# lllc.net
KiCad netlist of a schematic drawn in EAGLE
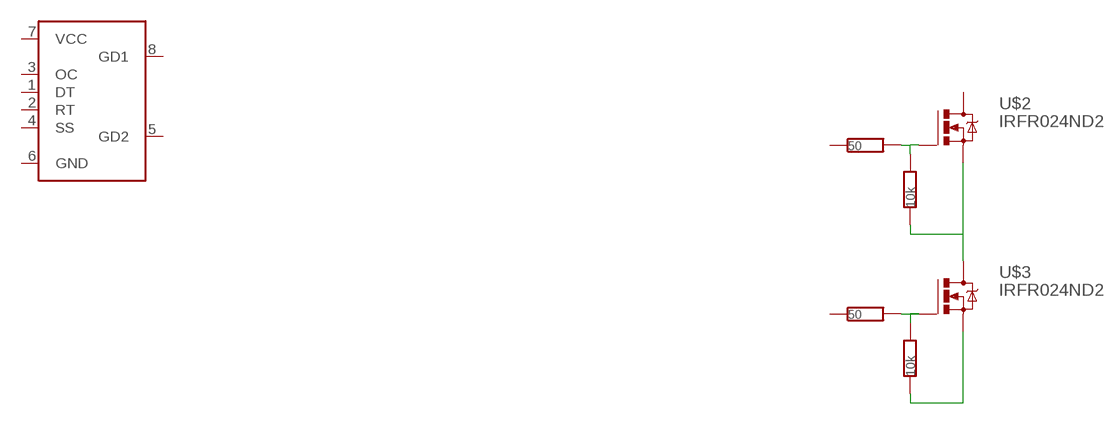
[diagram p0: schematic, sheet 1]

(export (version "E")
  (design (tool "Eeschema 10.0.6"))
  (components
    (comp (ref "R1")
      (value "50")
      (footprint "eagle-import:R0805")
      (libsource (lib "eagle-import") (part "R0805"))
    )
    (comp (ref "R2")
      (value "50")
      (footprint "eagle-import:R0805")
      (libsource (lib "eagle-import") (part "R0805"))
    )
    (comp (ref "R3")
      (value "10k")
      (footprint "eagle-import:R0805")
      (libsource (lib "eagle-import") (part "R0805"))
    )
    (comp (ref "R4")
      (value "10k")
      (footprint "eagle-import:R0805")
      (libsource (lib "eagle-import") (part "R0805"))
    )
    (comp (ref "U$1")
      (value "TPS92020")
      (footprint "eagle-import:SO08")
      (libsource (lib "eagle-import") (part "TPS92020"))
    )
    (comp (ref "U$2")
      (value "IRFR024ND2")
      (footprint "eagle-import:D2PACK")
      (libsource (lib "eagle-import") (part "IRFR024ND2"))
    )
    (comp (ref "U$3")
      (value "IRFR024ND2")
      (footprint "eagle-import:D2PACK")
      (libsource (lib "eagle-import") (part "IRFR024ND2"))
    )
  )
  (nets
    (net (code "1") (name "Net-(U$2-G)") (class "Default")
      (node (ref "R1") (pin "2") (pinfunction "2_2") (pintype "passive"))
      (node (ref "R3") (pin "2") (pinfunction "2_2") (pintype "passive"))
      (node (ref "U$2") (pin "1") (pinfunction "G_1") (pintype "passive"))
    )
    (net (code "2") (name "Net-(U$2-S)") (class "Default")
      (node (ref "R3") (pin "1") (pinfunction "1_1") (pintype "passive"))
      (node (ref "U$2") (pin "3") (pinfunction "S_3") (pintype "passive"))
      (node (ref "U$3") (pin "2") (pinfunction "D_2") (pintype "passive"))
    )
    (net (code "3") (name "Net-(U$3-G)") (class "Default")
      (node (ref "R2") (pin "2") (pinfunction "2_2") (pintype "passive"))
      (node (ref "R4") (pin "2") (pinfunction "2_2") (pintype "passive"))
      (node (ref "U$3") (pin "1") (pinfunction "G_1") (pintype "passive"))
    )
    (net (code "4") (name "Net-(U$3-S)") (class "Default")
      (node (ref "R4") (pin "1") (pinfunction "1_1") (pintype "passive"))
      (node (ref "U$3") (pin "3") (pinfunction "S_3") (pintype "passive"))
    )
    (net (code "5") (name "unconnected-(R1-Pad1)") (class "Default")
      (node (ref "R1") (pin "1") (pinfunction "1_1") (pintype "passive"))
    )
    (net (code "6") (name "unconnected-(R2-Pad1)") (class "Default")
      (node (ref "R2") (pin "1") (pinfunction "1_1") (pintype "passive"))
    )
    (net (code "7") (name "unconnected-(U$1-DT-Pad1)") (class "Default")
      (node (ref "U$1") (pin "1") (pinfunction "DT_1") (pintype "bidirectional"))
    )
    (net (code "8") (name "unconnected-(U$1-GD1-Pad8)") (class "Default")
      (node (ref "U$1") (pin "8") (pinfunction "GD1_8") (pintype "bidirectional"))
    )
    (net (code "9") (name "unconnected-(U$1-GD2-Pad5)") (class "Default")
      (node (ref "U$1") (pin "5") (pinfunction "GD2_5") (pintype "bidirectional"))
    )
    (net (code "10") (name "unconnected-(U$1-GND-Pad6)") (class "Default")
      (node (ref "U$1") (pin "6") (pinfunction "GND_6") (pintype "bidirectional"))
    )
    (net (code "11") (name "unconnected-(U$1-OC-Pad3)") (class "Default")
      (node (ref "U$1") (pin "3") (pinfunction "OC_3") (pintype "bidirectional"))
    )
    (net (code "12") (name "unconnected-(U$1-RT-Pad2)") (class "Default")
      (node (ref "U$1") (pin "2") (pinfunction "RT_2") (pintype "bidirectional"))
    )
    (net (code "13") (name "unconnected-(U$1-SS-Pad4)") (class "Default")
      (node (ref "U$1") (pin "4") (pinfunction "SS_4") (pintype "bidirectional"))
    )
    (net (code "14") (name "unconnected-(U$1-VCC-Pad7)") (class "Default")
      (node (ref "U$1") (pin "7") (pinfunction "VCC_7") (pintype "bidirectional"))
    )
    (net (code "15") (name "unconnected-(U$2-D-Pad2)") (class "Default")
      (node (ref "U$2") (pin "2") (pinfunction "D_2") (pintype "passive"))
    )
  )
)
